# Sheet1.net
KiCad netlist of a schematic drawn in Altium Designer
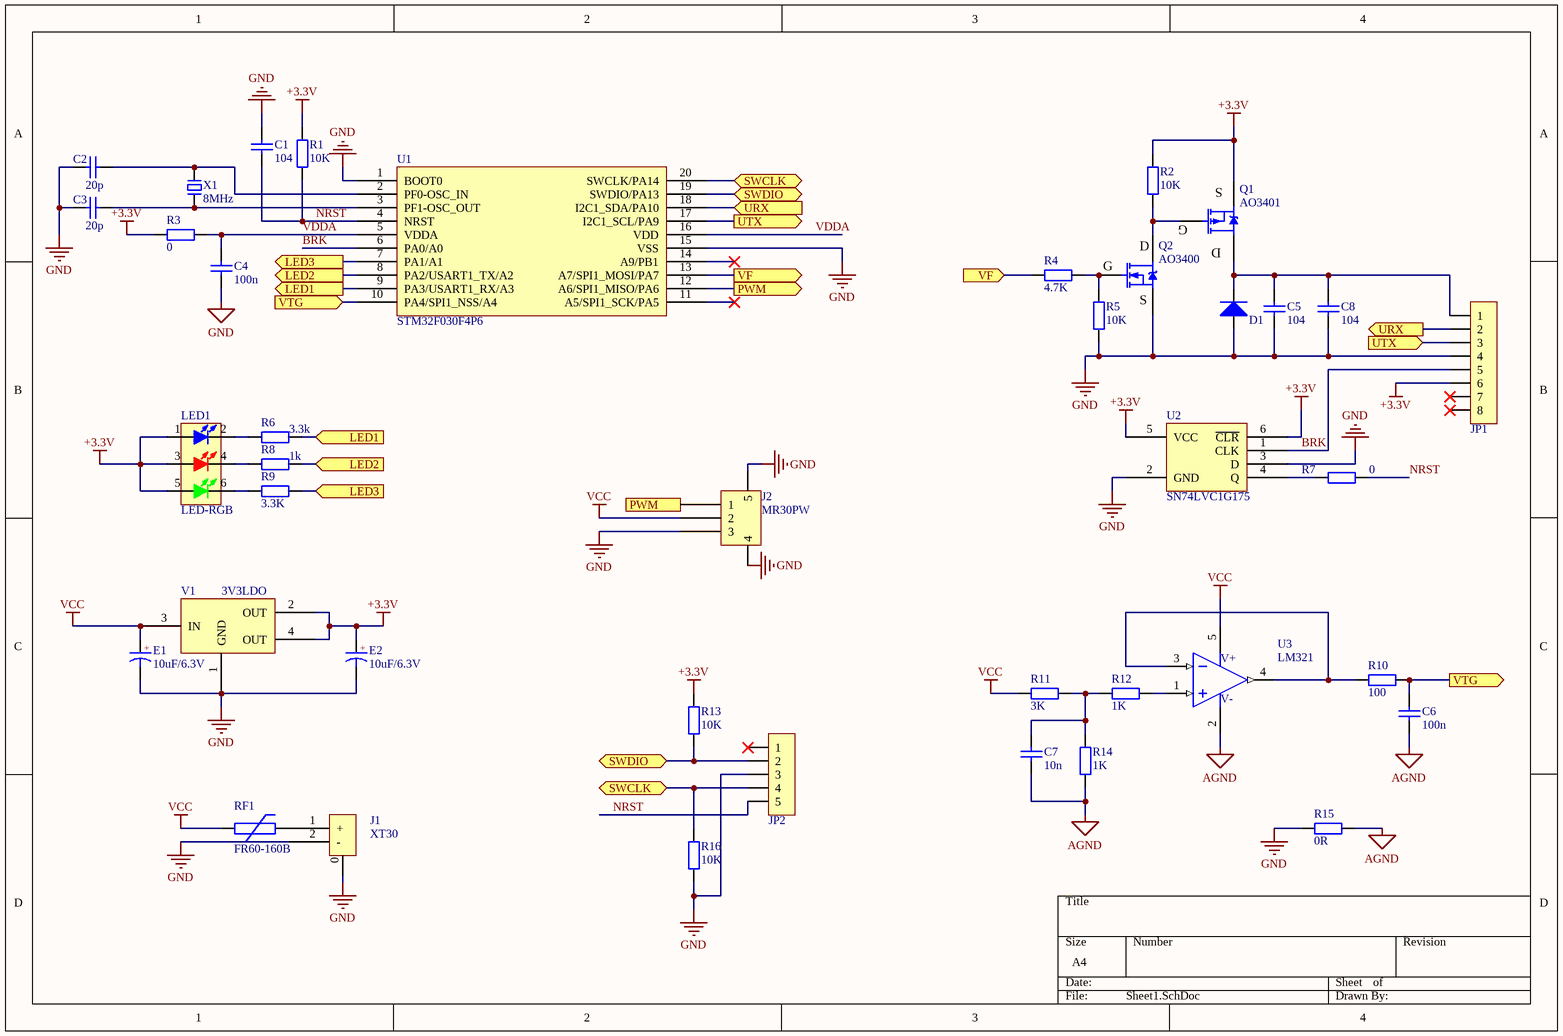
[diagram p0: Sheet1.SchDoc]

(export (version "E")
  (design (tool "Eeschema 10.0.6"))
  (components
    (comp (ref "C1")
      (value "104")
      (footprint "C0603_L")
      (description "贴片电容/MLCC电容")
      (libsource (lib "0.1 - 电阻-电容-电感-晶振-晶体-磁珠-电位器-法拉电容-馈通电容") (part "C"))
    )
    (comp (ref "C2")
      (value "20p")
      (footprint "C0603_L")
      (description "贴片电容/MLCC电容")
      (libsource (lib "0.1 - 电阻-电容-电感-晶振-晶体-磁珠-电位器-法拉电容-馈通电容") (part "C"))
    )
    (comp (ref "C3")
      (value "20p")
      (footprint "C0603_L")
      (description "贴片电容/MLCC电容")
      (libsource (lib "0.1 - 电阻-电容-电感-晶振-晶体-磁珠-电位器-法拉电容-馈通电容") (part "C"))
    )
    (comp (ref "C4")
      (value "100n")
      (footprint "C0603_L")
      (description "贴片电容/MLCC电容")
      (libsource (lib "0.1 - 电阻-电容-电感-晶振-晶体-磁珠-电位器-法拉电容-馈通电容") (part "C"))
    )
    (comp (ref "C5")
      (value "104")
      (footprint "C0805_L")
      (description "贴片电容/MLCC电容")
      (libsource (lib "0.1 - 电阻-电容-电感-晶振-晶体-磁珠-电位器-法拉电容-馈通电容") (part "C"))
    )
    (comp (ref "C6")
      (value "100n")
      (footprint "C0603_L")
      (description "贴片电容/MLCC电容")
      (libsource (lib "0.1 - 电阻-电容-电感-晶振-晶体-磁珠-电位器-法拉电容-馈通电容") (part "C"))
    )
    (comp (ref "C7")
      (value "10n")
      (footprint "C0603_L")
      (description "贴片电容/MLCC电容")
      (libsource (lib "0.1 - 电阻-电容-电感-晶振-晶体-磁珠-电位器-法拉电容-馈通电容") (part "C"))
    )
    (comp (ref "C8")
      (value "104")
      (footprint "C0805_L")
      (description "贴片电容/MLCC电容")
      (libsource (lib "0.1 - 电阻-电容-电感-晶振-晶体-磁珠-电位器-法拉电容-馈通电容") (part "C"))
    )
    (comp (ref "D1")
      (value "TVS")
      (footprint "SOD-123")
      (description "TVS通用")
      (libsource (lib "0.2 - 二极管-TVS-ESD-整流桥-放电管") (part "TVS"))
    )
    (comp (ref "E1")
      (value "10uF/6.3V")
      (footprint "C_3216")
      (description "贴片钽电容")
      (libsource (lib "0.1 - 电阻-电容-电感-晶振-晶体-磁珠-电位器-法拉电容-馈通电容") (part "CT"))
    )
    (comp (ref "E2")
      (value "10uF/6.3V")
      (footprint "C_3216")
      (description "贴片钽电容")
      (libsource (lib "0.1 - 电阻-电容-电感-晶振-晶体-磁珠-电位器-法拉电容-馈通电容") (part "CT"))
    )
    (comp (ref "J1") (value "XT30") (footprint "XT30PW-F") (libsource (lib "ifan-private") (part "XT30")))
    (comp (ref "J2")
      (value "MR30PW")
      (footprint "MR30PW-FB")
      (libsource (lib "ifan-private") (part "MR30PW"))
    )
    (comp (ref "JP1")
      (value "HDR-1X8")
      (footprint "MX1.25-WT-8P")
      (description "8P连接器")
      (libsource (lib "5.1 - 1.25mm连接器(FPC1.25_GH1.25_MX1.25)") (part "Header 8"))
    )
    (comp (ref "JP2")
      (value "HDR-1X5")
      (footprint "XH2.54-LS-5P")
      (description "5P接插件")
      (libsource (lib "5.5 - 2.54mm连接器(KF2EDGK_XH2.54_2.54排针排母)") (part "Header 5"))
    )
    (comp (ref "LED1")
      (value "LED-RGB")
      (footprint "LED 5050")
      (description "5050三基色LED")
      (libsource (lib "0.3 - LED发光二极管-IR二极管_接收管-光耦") (part "LED-RGB 5050"))
    )
    (comp (ref "Q1")
      (value "AO3401")
      (footprint "SOT23-3M")
      (description "P沟道 30V/4.2A")
      (libsource (lib "0.4 - 三极管-场效应管-可控硅") (part "AO3401"))
    )
    (comp (ref "Q2")
      (value "AO3400")
      (footprint "SOT23-3M")
      (description "N沟道 30V/4.2A")
      (libsource (lib "0.4 - 三极管-场效应管-可控硅") (part "AO3400"))
    )
    (comp (ref "R1")
      (value "10K")
      (footprint "R0603_L")
      (description "贴片电阻")
      (libsource (lib "0.1 - 电阻-电容-电感-晶振-晶体-磁珠-电位器-法拉电容-馈通电容") (part "R"))
    )
    (comp (ref "R2")
      (value "10K")
      (footprint "R0603_L")
      (description "贴片电阻")
      (libsource (lib "0.1 - 电阻-电容-电感-晶振-晶体-磁珠-电位器-法拉电容-馈通电容") (part "R"))
    )
    (comp (ref "R3")
      (value "0")
      (footprint "R0603_L")
      (description "贴片电阻")
      (libsource (lib "0.1 - 电阻-电容-电感-晶振-晶体-磁珠-电位器-法拉电容-馈通电容") (part "R"))
    )
    (comp (ref "R4")
      (value "4.7K")
      (footprint "R0603_L")
      (description "贴片电阻")
      (libsource (lib "0.1 - 电阻-电容-电感-晶振-晶体-磁珠-电位器-法拉电容-馈通电容") (part "R"))
    )
    (comp (ref "R5")
      (value "10K")
      (footprint "R0603_L")
      (description "贴片电阻")
      (libsource (lib "0.1 - 电阻-电容-电感-晶振-晶体-磁珠-电位器-法拉电容-馈通电容") (part "R"))
    )
    (comp (ref "R6")
      (value "3.3k")
      (footprint "R0603_L")
      (description "贴片电阻")
      (libsource (lib "0.1 - 电阻-电容-电感-晶振-晶体-磁珠-电位器-法拉电容-馈通电容") (part "R"))
    )
    (comp (ref "R7")
      (value "0")
      (footprint "R0603_L")
      (description "贴片电阻")
      (libsource (lib "0.1 - 电阻-电容-电感-晶振-晶体-磁珠-电位器-法拉电容-馈通电容") (part "R"))
    )
    (comp (ref "R8")
      (value "1k")
      (footprint "R0603_L")
      (description "贴片电阻")
      (libsource (lib "0.1 - 电阻-电容-电感-晶振-晶体-磁珠-电位器-法拉电容-馈通电容") (part "R"))
    )
    (comp (ref "R9")
      (value "3.3K")
      (footprint "R0603_L")
      (description "贴片电阻")
      (libsource (lib "0.1 - 电阻-电容-电感-晶振-晶体-磁珠-电位器-法拉电容-馈通电容") (part "R"))
    )
    (comp (ref "R10")
      (value "100")
      (footprint "R0603_L")
      (description "贴片电阻")
      (libsource (lib "0.1 - 电阻-电容-电感-晶振-晶体-磁珠-电位器-法拉电容-馈通电容") (part "R"))
    )
    (comp (ref "R11")
      (value "3K")
      (footprint "R0603_L")
      (description "贴片电阻")
      (libsource (lib "0.1 - 电阻-电容-电感-晶振-晶体-磁珠-电位器-法拉电容-馈通电容") (part "R"))
    )
    (comp (ref "R12")
      (value "1K")
      (footprint "R0603_L")
      (description "贴片电阻")
      (libsource (lib "0.1 - 电阻-电容-电感-晶振-晶体-磁珠-电位器-法拉电容-馈通电容") (part "R"))
    )
    (comp (ref "R13")
      (value "10K")
      (footprint "R0603_L")
      (description "贴片电阻")
      (libsource (lib "0.1 - 电阻-电容-电感-晶振-晶体-磁珠-电位器-法拉电容-馈通电容") (part "R"))
    )
    (comp (ref "R14")
      (value "1K")
      (footprint "R0603_L")
      (description "贴片电阻")
      (libsource (lib "0.1 - 电阻-电容-电感-晶振-晶体-磁珠-电位器-法拉电容-馈通电容") (part "R"))
    )
    (comp (ref "R15")
      (value "0R")
      (footprint "R0603_L")
      (description "贴片电阻")
      (libsource (lib "0.1 - 电阻-电容-电感-晶振-晶体-磁珠-电位器-法拉电容-馈通电容") (part "R"))
    )
    (comp (ref "R16")
      (value "10K")
      (footprint "R0603_L")
      (description "贴片电阻")
      (libsource (lib "0.1 - 电阻-电容-电感-晶振-晶体-磁珠-电位器-法拉电容-馈通电容") (part "R"))
    )
    (comp (ref "RF1")
      (value "FR60-160B")
      (footprint "FU 0805")
      (description "PPTC自恢复保险丝")
      (libsource (lib "0.5 - 按键_开关_蜂鸣器_保险丝_电池_测试点_Mark点_铜柱") (part "FU-PPTC"))
    )
    (comp (ref "U1")
      (value "STM32F030F4P6")
      (footprint "TSSOP20_N")
      (description "Flash: 16K/RAM: 4K/IO: 15")
      (libsource (lib "2.3 - STM32 F0系列单片机") (part "STM32F030F4"))
    )
    (comp (ref "U2")
      (value "SN74LVC1G175")
      (footprint "SOT-23-6")
      (description "单路D触发器")
      (libsource (lib "ifan-private") (part "SN74LVC1G175"))
    )
    (comp (ref "U3")
      (value "LM321")
      (footprint "SOT23-5M")
      (description "Low Power Single Op Amp, 5-pin SOT-23")
      (libsource (lib "0.8 - 常见芯片") (part "LM321"))
    )
    (comp (ref "V1")
      (value "3V3LDO")
      (footprint "SOT223_M")
      (description "低压差线性稳压芯片（4脚是out）")
      (libsource (lib "ifan-private") (part "CJT1117B-3.3"))
    )
    (comp (ref "X1")
      (value "8MHz")
      (footprint "HC-49S")
      (description "2脚无源晶振(谐振器）")
      (libsource (lib "0.1 - 电阻-电容-电感-晶振-晶体-磁珠-电位器-法拉电容-馈通电容") (part "XTAL-2P"))
    )
  )
  (nets
    (net (code "1") (name "+3.3V") (class "Default")
      (node (ref "E2") (pin "1") (pinfunction "A_1") (pintype "passive"))
      (node (ref "JP1") (pin "6") (pinfunction "6_6") (pintype "passive"))
      (node (ref "LED1") (pin "1") (pinfunction "BULE_A_1") (pintype "passive"))
      (node (ref "LED1") (pin "3") (pinfunction "RED_A_3") (pintype "passive"))
      (node (ref "LED1") (pin "5") (pinfunction "GREEN_A_5") (pintype "passive"))
      (node (ref "Q1") (pin "2") (pinfunction "S_2") (pintype "passive"))
      (node (ref "R1") (pin "2") (pinfunction "2_2") (pintype "passive"))
      (node (ref "R13") (pin "2") (pinfunction "2_2") (pintype "passive"))
      (node (ref "R2") (pin "2") (pinfunction "2_2") (pintype "passive"))
      (node (ref "R3") (pin "1") (pinfunction "1_1") (pintype "passive"))
      (node (ref "U2") (pin "5") (pinfunction "VCC_5") (pintype "passive"))
      (node (ref "U2") (pin "6") (pinfunction "~{CLR}_6") (pintype "passive"))
      (node (ref "V1") (pin "2") (pinfunction "OUT_2") (pintype "passive"))
      (node (ref "V1") (pin "4") (pinfunction "OUT_4") (pintype "passive"))
    )
    (net (code "2") (name "/BRK") (class "Default")
      (node (ref "JP1") (pin "5") (pinfunction "5_5") (pintype "passive"))
      (node (ref "U1") (pin "6") (pinfunction "PA0/A0_6") (pintype "passive"))
      (node (ref "U2") (pin "1") (pinfunction "CLK_1") (pintype "passive"))
    )
    (net (code "3") (name "/LED1") (class "Default")
      (node (ref "R6") (pin "2") (pinfunction "2_2") (pintype "passive"))
      (node (ref "U1") (pin "9") (pinfunction "PA3/USART1_RX/A3_9") (pintype "passive"))
    )
    (net (code "4") (name "/LED2") (class "Default")
      (node (ref "R8") (pin "2") (pinfunction "2_2") (pintype "passive"))
      (node (ref "U1") (pin "8") (pinfunction "PA2/USART1_TX/A2_8") (pintype "passive"))
    )
    (net (code "5") (name "/LED3") (class "Default")
      (node (ref "R9") (pin "2") (pinfunction "2_2") (pintype "passive"))
      (node (ref "U1") (pin "7") (pinfunction "PA1/A1_7") (pintype "passive"))
    )
    (net (code "6") (name "/NRST") (class "Default")
      (node (ref "C1") (pin "1") (pinfunction "1_1") (pintype "passive"))
      (node (ref "JP2") (pin "5") (pinfunction "5_5") (pintype "passive"))
      (node (ref "R1") (pin "1") (pinfunction "1_1") (pintype "passive"))
      (node (ref "R7") (pin "2") (pinfunction "2_2") (pintype "passive"))
      (node (ref "U1") (pin "4") (pinfunction "NRST_4") (pintype "passive"))
    )
    (net (code "7") (name "/PWM") (class "Default")
      (node (ref "J2") (pin "1") (pinfunction "1_1") (pintype "passive"))
      (node (ref "U1") (pin "12") (pinfunction "A6/SPI1_MISO/PA6_12") (pintype "passive"))
    )
    (net (code "8") (name "/SWCLK") (class "Default")
      (node (ref "JP2") (pin "4") (pinfunction "4_4") (pintype "passive"))
      (node (ref "R16") (pin "2") (pinfunction "2_2") (pintype "passive"))
      (node (ref "U1") (pin "20") (pinfunction "SWCLK/PA14_20") (pintype "passive"))
    )
    (net (code "9") (name "/SWDIO") (class "Default")
      (node (ref "JP2") (pin "2") (pinfunction "2_2") (pintype "passive"))
      (node (ref "R13") (pin "1") (pinfunction "1_1") (pintype "passive"))
      (node (ref "U1") (pin "19") (pinfunction "SWDIO/PA13_19") (pintype "passive"))
    )
    (net (code "10") (name "/URX") (class "Default")
      (node (ref "JP1") (pin "2") (pinfunction "2_2") (pintype "passive"))
      (node (ref "U1") (pin "18") (pinfunction "I2C1_SDA/PA10_18") (pintype "passive"))
    )
    (net (code "11") (name "/UTX") (class "Default")
      (node (ref "JP1") (pin "3") (pinfunction "3_3") (pintype "passive"))
      (node (ref "U1") (pin "17") (pinfunction "I2C1_SCL/PA9_17") (pintype "passive"))
    )
    (net (code "12") (name "/VDDA") (class "Default")
      (node (ref "C4") (pin "2") (pinfunction "2_2") (pintype "passive"))
      (node (ref "R3") (pin "2") (pinfunction "2_2") (pintype "passive"))
      (node (ref "U1") (pin "16") (pinfunction "VDD_16") (pintype "passive"))
      (node (ref "U1") (pin "5") (pinfunction "VDDA_5") (pintype "passive"))
    )
    (net (code "13") (name "/VF") (class "Default")
      (node (ref "R4") (pin "1") (pinfunction "1_1") (pintype "passive"))
      (node (ref "U1") (pin "13") (pinfunction "A7/SPI1_MOSI/PA7_13") (pintype "passive"))
    )
    (net (code "14") (name "/VTG") (class "Default")
      (node (ref "C6") (pin "2") (pinfunction "2_2") (pintype "passive"))
      (node (ref "R10") (pin "2") (pinfunction "2_2") (pintype "passive"))
      (node (ref "U1") (pin "10") (pinfunction "PA4/SPI1_NSS/A4_10") (pintype "passive"))
    )
    (net (code "15") (name "AGND") (class "Default")
      (node (ref "C6") (pin "1") (pinfunction "1_1") (pintype "passive"))
      (node (ref "C7") (pin "1") (pinfunction "1_1") (pintype "passive"))
      (node (ref "R14") (pin "1") (pinfunction "1_1") (pintype "passive"))
      (node (ref "R15") (pin "2") (pinfunction "2_2") (pintype "passive"))
      (node (ref "U3") (pin "2") (pinfunction "V-_2") (pintype "power_in"))
    )
    (net (code "16") (name "GND") (class "Default")
      (node (ref "C1") (pin "2") (pinfunction "2_2") (pintype "passive"))
      (node (ref "C2") (pin "1") (pinfunction "1_1") (pintype "passive"))
      (node (ref "C3") (pin "1") (pinfunction "1_1") (pintype "passive"))
      (node (ref "C4") (pin "1") (pinfunction "1_1") (pintype "passive"))
      (node (ref "C5") (pin "1") (pinfunction "1_1") (pintype "passive"))
      (node (ref "C8") (pin "1") (pinfunction "1_1") (pintype "passive"))
      (node (ref "D1") (pin "1") (pinfunction "A_1") (pintype "passive"))
      (node (ref "E1") (pin "2") (pinfunction "K_2") (pintype "passive"))
      (node (ref "E2") (pin "2") (pinfunction "K_2") (pintype "passive"))
      (node (ref "J1") (pin "2") (pinfunction "-_2") (pintype "passive"))
      (node (ref "J2") (pin "3") (pinfunction "3_3") (pintype "passive"))
      (node (ref "J2") (pin "4") (pinfunction "4_4") (pintype "passive"))
      (node (ref "J2") (pin "5") (pinfunction "5_5") (pintype "passive"))
      (node (ref "JP1") (pin "4") (pinfunction "4_4") (pintype "passive"))
      (node (ref "JP2") (pin "3") (pinfunction "3_3") (pintype "passive"))
      (node (ref "Q2") (pin "2") (pinfunction "S_2") (pintype "passive"))
      (node (ref "R15") (pin "1") (pinfunction "1_1") (pintype "passive"))
      (node (ref "R16") (pin "1") (pinfunction "1_1") (pintype "passive"))
      (node (ref "R5") (pin "1") (pinfunction "1_1") (pintype "passive"))
      (node (ref "U1") (pin "1") (pinfunction "BOOT0_1") (pintype "passive"))
      (node (ref "U1") (pin "15") (pinfunction "VSS_15") (pintype "passive"))
      (node (ref "U2") (pin "2") (pinfunction "GND_2") (pintype "passive"))
      (node (ref "U2") (pin "3") (pinfunction "D_3") (pintype "passive"))
      (node (ref "V1") (pin "1") (pinfunction "GND_1") (pintype "passive"))
    )
    (net (code "17") (name "Net-(C7-Pad2)") (class "Default")
      (node (ref "C7") (pin "2") (pinfunction "2_2") (pintype "passive"))
      (node (ref "R11") (pin "2") (pinfunction "2_2") (pintype "passive"))
      (node (ref "R12") (pin "1") (pinfunction "1_1") (pintype "passive"))
      (node (ref "R14") (pin "2") (pinfunction "2_2") (pintype "passive"))
    )
    (net (code "18") (name "Net-(D1-K)") (class "Default")
      (node (ref "C5") (pin "2") (pinfunction "2_2") (pintype "passive"))
      (node (ref "C8") (pin "2") (pinfunction "2_2") (pintype "passive"))
      (node (ref "D1") (pin "2") (pinfunction "K_2") (pintype "passive"))
      (node (ref "JP1") (pin "1") (pinfunction "1_1") (pintype "passive"))
      (node (ref "Q1") (pin "3") (pinfunction "D_3") (pintype "passive"))
    )
    (net (code "19") (name "Net-(J1-+)") (class "Default")
      (node (ref "J1") (pin "1") (pinfunction "+_1") (pintype "passive"))
      (node (ref "RF1") (pin "2") (pinfunction "2_2") (pintype "passive"))
    )
    (net (code "20") (name "Net-(LED1-BULE_K)") (class "Default")
      (node (ref "LED1") (pin "2") (pinfunction "BULE_K_2") (pintype "passive"))
      (node (ref "R6") (pin "1") (pinfunction "1_1") (pintype "passive"))
    )
    (net (code "21") (name "Net-(LED1-GREEN_K)") (class "Default")
      (node (ref "LED1") (pin "6") (pinfunction "GREEN_K_6") (pintype "passive"))
      (node (ref "R9") (pin "1") (pinfunction "1_1") (pintype "passive"))
    )
    (net (code "22") (name "Net-(LED1-RED_K)") (class "Default")
      (node (ref "LED1") (pin "4") (pinfunction "RED_K_4") (pintype "passive"))
      (node (ref "R8") (pin "1") (pinfunction "1_1") (pintype "passive"))
    )
    (net (code "23") (name "Net-(Q1-G)") (class "Default")
      (node (ref "Q1") (pin "1") (pinfunction "G_1") (pintype "passive"))
      (node (ref "Q2") (pin "3") (pinfunction "D_3") (pintype "passive"))
      (node (ref "R2") (pin "1") (pinfunction "1_1") (pintype "passive"))
    )
    (net (code "24") (name "Net-(Q2-G)") (class "Default")
      (node (ref "Q2") (pin "1") (pinfunction "G_1") (pintype "passive"))
      (node (ref "R4") (pin "2") (pinfunction "2_2") (pintype "passive"))
      (node (ref "R5") (pin "2") (pinfunction "2_2") (pintype "passive"))
    )
    (net (code "25") (name "Net-(U1-PF0-OSC_IN)") (class "Default")
      (node (ref "C2") (pin "2") (pinfunction "2_2") (pintype "passive"))
      (node (ref "U1") (pin "2") (pinfunction "PF0-OSC_IN_2") (pintype "passive"))
      (node (ref "X1") (pin "2") (pinfunction "2_2") (pintype "passive"))
    )
    (net (code "26") (name "Net-(U1-PF1-OSC_OUT)") (class "Default")
      (node (ref "C3") (pin "2") (pinfunction "2_2") (pintype "passive"))
      (node (ref "U1") (pin "3") (pinfunction "PF1-OSC_OUT_3") (pintype "passive"))
      (node (ref "X1") (pin "1") (pinfunction "1_1") (pintype "passive"))
    )
    (net (code "27") (name "Net-(U2-Q)") (class "Default")
      (node (ref "R7") (pin "1") (pinfunction "1_1") (pintype "passive"))
      (node (ref "U2") (pin "4") (pinfunction "Q_4") (pintype "passive"))
    )
    (net (code "28") (name "Net-(U3-IN+)") (class "Default")
      (node (ref "R12") (pin "2") (pinfunction "2_2") (pintype "passive"))
      (node (ref "U3") (pin "1") (pinfunction "IN+_1") (pintype "input"))
    )
    (net (code "29") (name "Net-(U3-IN-)") (class "Default")
      (node (ref "R10") (pin "1") (pinfunction "1_1") (pintype "passive"))
      (node (ref "U3") (pin "3") (pinfunction "IN-_3") (pintype "input"))
      (node (ref "U3") (pin "4") (pinfunction "OUT_4") (pintype "output"))
    )
    (net (code "30") (name "VCC") (class "Default")
      (node (ref "E1") (pin "1") (pinfunction "A_1") (pintype "passive"))
      (node (ref "J2") (pin "2") (pinfunction "2_2") (pintype "passive"))
      (node (ref "R11") (pin "1") (pinfunction "1_1") (pintype "passive"))
      (node (ref "RF1") (pin "1") (pinfunction "1_1") (pintype "passive"))
      (node (ref "U3") (pin "5") (pinfunction "V+_5") (pintype "power_in"))
      (node (ref "V1") (pin "3") (pinfunction "IN_3") (pintype "passive"))
    )
    (net (code "31") (name "unconnected-(J1-GND-Pad0)") (class "Default")
      (node (ref "J1") (pin "0") (pinfunction "GND_0") (pintype "passive"))
    )
    (net (code "32") (name "unconnected-(JP1-Pad7)") (class "Default")
      (node (ref "JP1") (pin "7") (pinfunction "7_7") (pintype "passive+no_connect"))
    )
    (net (code "33") (name "unconnected-(JP1-Pad8)") (class "Default")
      (node (ref "JP1") (pin "8") (pinfunction "8_8") (pintype "passive+no_connect"))
    )
    (net (code "34") (name "unconnected-(JP2-Pad1)") (class "Default")
      (node (ref "JP2") (pin "1") (pinfunction "1_1") (pintype "passive+no_connect"))
    )
    (net (code "35") (name "unconnected-(U1-A5{slash}SPI1_SCK{slash}PA5-Pad11)") (class "Default")
      (node (ref "U1") (pin "11") (pinfunction "A5/SPI1_SCK/PA5_11") (pintype "passive+no_connect"))
    )
    (net (code "36") (name "unconnected-(U1-A9{slash}PB1-Pad14)") (class "Default")
      (node (ref "U1") (pin "14") (pinfunction "A9/PB1_14") (pintype "passive+no_connect"))
    )
  )
)
